# USB_Module_SchDoc.net
KiCad netlist of a schematic drawn in Altium Designer
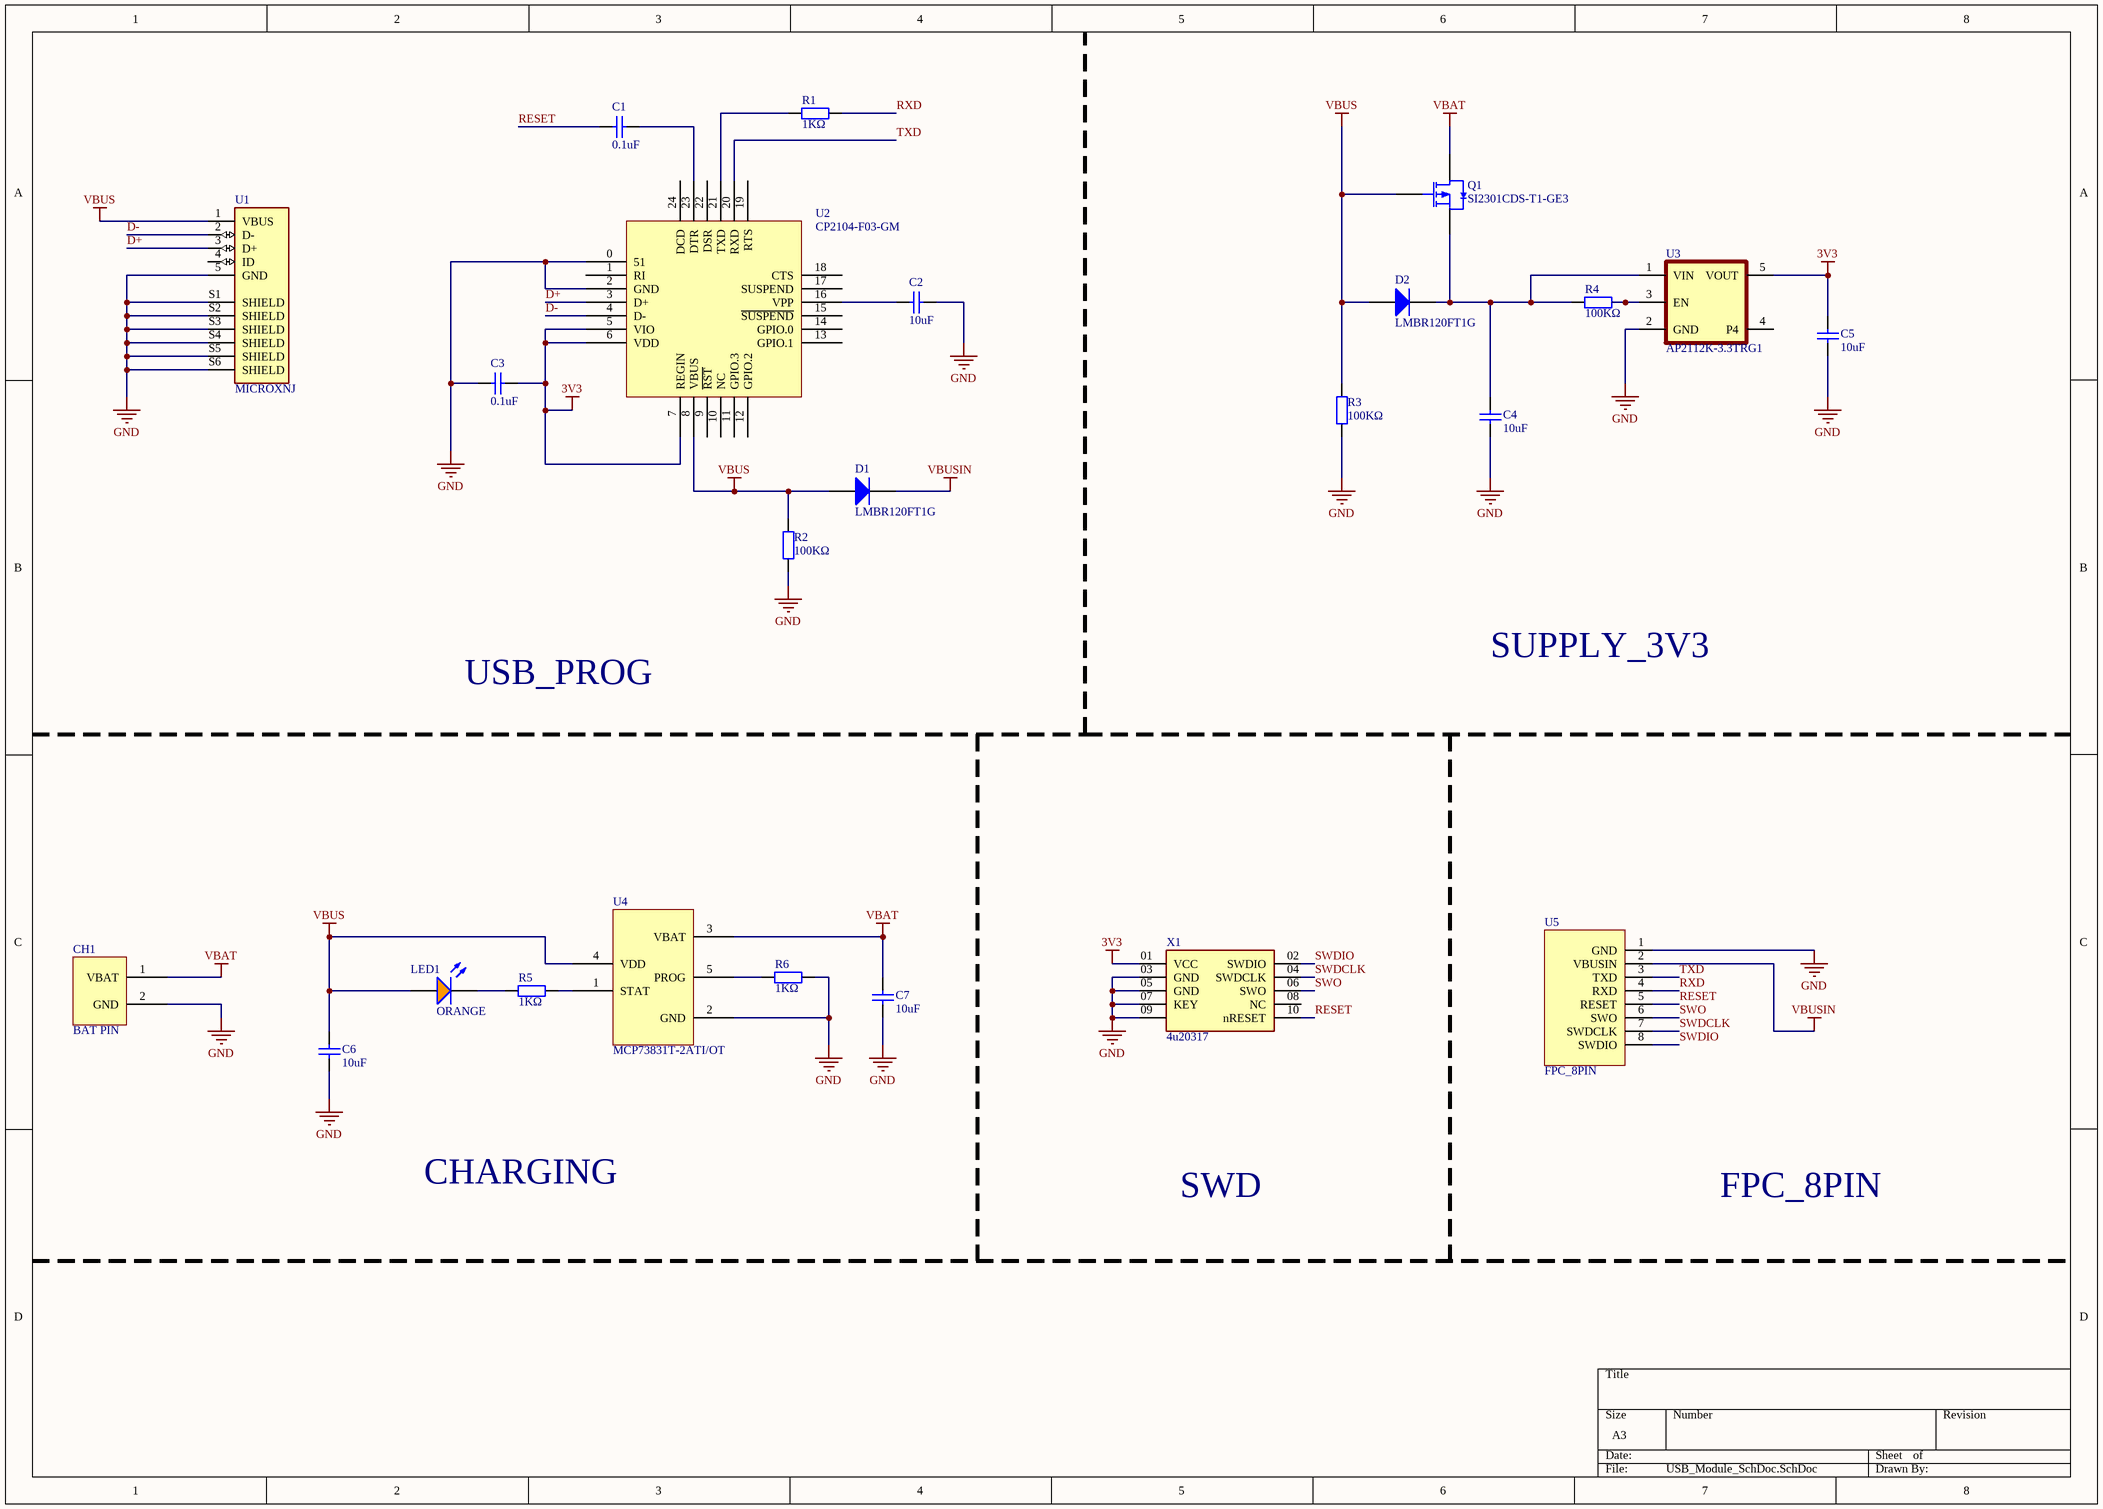
[diagram p0: USB_Module_SchDoc.SchDoc]

(export (version "E")
  (design (tool "Eeschema 10.0.6"))
  (components
    (comp (ref "C1")
      (value "0.1uF")
      (footprint "0603_C")
      (description "capacitance")
      (libsource (lib "magjoint_MCU") (part "CAP_0.1uF"))
    )
    (comp (ref "C2")
      (value "10uF")
      (footprint "0805_C")
      (description "capacitance")
      (libsource (lib "magjoint_MCU") (part "CAP_10uF"))
    )
    (comp (ref "C3")
      (value "0.1uF")
      (footprint "0603_C")
      (description "capacitance")
      (libsource (lib "magjoint_MCU") (part "CAP_0.1uF"))
    )
    (comp (ref "C4")
      (value "10uF")
      (footprint "0805_C")
      (description "capacitance")
      (libsource (lib "magjoint_MCU") (part "CAP_10uF"))
    )
    (comp (ref "C5")
      (value "10uF")
      (footprint "0805_C")
      (description "capacitance")
      (libsource (lib "magjoint_MCU") (part "CAP_10uF"))
    )
    (comp (ref "C6")
      (value "10uF")
      (footprint "0805_C")
      (description "capacitance")
      (libsource (lib "magjoint_MCU") (part "CAP_10uF"))
    )
    (comp (ref "C7")
      (value "10uF")
      (footprint "0805_C")
      (description "capacitance")
      (libsource (lib "magjoint_MCU") (part "CAP_10uF"))
    )
    (comp (ref "CH1")
      (value "BAT PIN")
      (footprint "BAT_MX 1.25-WI-2P")
      (description "button cell battary holder BS-08-B2AA025")
      (libsource (lib "magjoint_MCU") (part "BAT"))
    )
    (comp (ref "D1")
      (value "LMBR120FT1G")
      (footprint "SOD-123")
      (description "schottky diode")
      (libsource (lib "magjoint_MCU") (part "DIO_5"))
    )
    (comp (ref "D2")
      (value "LMBR120FT1G")
      (footprint "SOD-123")
      (description "schottky diode")
      (libsource (lib "magjoint_MCU") (part "DIO_5"))
    )
    (comp (ref "LED1")
      (value "ORANGE")
      (footprint "0603_LED_S1")
      (description "LED")
      (libsource (lib "MAGNETO") (part "LED_ORANGE"))
    )
    (comp (ref "Q1")
      (value "SI2301CDS-T1-GE3")
      (footprint "SOT-23(SOT-23-3)")
      (description "field effect tube")
      (libsource (lib "magjoint_MCU") (part "MOS"))
    )
    (comp (ref "R1")
      (value "1KΩ")
      (footprint "0603_R")
      (description "resistance")
      (libsource (lib "magjoint_MCU") (part "RES_1KΩ"))
    )
    (comp (ref "R2")
      (value "100KΩ")
      (footprint "0603_R")
      (description "resistance")
      (libsource (lib "magjoint_MCU") (part "RES_100KΩ"))
    )
    (comp (ref "R3")
      (value "100KΩ")
      (footprint "0603_R")
      (description "resistance")
      (libsource (lib "magjoint_MCU") (part "RES_100KΩ"))
    )
    (comp (ref "R4")
      (value "100KΩ")
      (footprint "0603_R")
      (description "resistance")
      (libsource (lib "") (part "RES_100KΩ_1"))
    )
    (comp (ref "R5")
      (value "1KΩ")
      (footprint "0603_R")
      (description "resistance")
      (libsource (lib "magjoint_MCU") (part "RES_1KΩ"))
    )
    (comp (ref "R6")
      (value "1KΩ")
      (footprint "0603_R")
      (description "resistance")
      (libsource (lib "magjoint_MCU") (part "RES_1KΩ"))
    )
    (comp (ref "U1")
      (value "MICROXNJ")
      (footprint "SHOUHAN_MICROXNJ")
      (description "Micro USB")
      (libsource (lib "magjoint_MCU") (part "MICROXNJ"))
    )
    (comp (ref "U2")
      (value "CP2104-F03-GM")
      (footprint "QFN-24_4x4x05P")
      (description "USB chip")
      (libsource (lib "magjoint_MCU") (part "CP2104"))
    )
    (comp (ref "U3")
      (value "AP2112K-3.3TRG1")
      (footprint "SOT95P285X140-5N")
      (description "LDO_ low dropout linear regulator")
      (libsource (lib "magjoint_MCU") (part "AP2112K"))
    )
    (comp (ref "U4")
      (value "MCP73831T-2ATI/OT")
      (footprint "SOT95P280X145-5N")
      (description "Battery power management chip")
      (libsource (lib "MAGNETO") (part "MCP73831T"))
    )
    (comp (ref "U5")
      (value "FPC_8PIN")
      (footprint "FPC0.5 2H-WS-8P")
      (libsource (lib "magjoint_MCU") (part "FPC_8PIN"))
    )
    (comp (ref "X1")
      (value "4u20317")
      (footprint "TFM-105-12-S-D-A")
      (description "Serial Wire (SW-DP) Connector")
      (libsource (lib "magjoint_MCU") (part "JTAG-CORTEXBOXPOSTS"))
    )
  )
  (nets
    (net (code "1") (name "/D+") (class "Default")
      (node (ref "U1") (pin "3") (pinfunction "D+_3") (pintype "bidirectional"))
      (node (ref "U2") (pin "3") (pinfunction "D+_3") (pintype "passive"))
    )
    (net (code "2") (name "/D-") (class "Default")
      (node (ref "U1") (pin "2") (pinfunction "D-_2") (pintype "bidirectional"))
      (node (ref "U2") (pin "4") (pinfunction "D-_4") (pintype "passive"))
    )
    (net (code "3") (name "/RESET") (class "Default")
      (node (ref "C1") (pin "1") (pinfunction "1_1") (pintype "passive"))
      (node (ref "U5") (pin "5") (pinfunction "RESET_5") (pintype "passive"))
      (node (ref "X1") (pin "10") (pinfunction "nRESET_10") (pintype "passive"))
    )
    (net (code "4") (name "/RXD") (class "Default")
      (node (ref "R1") (pin "2") (pinfunction "2_2") (pintype "passive"))
      (node (ref "U5") (pin "4") (pinfunction "RXD_4") (pintype "passive"))
    )
    (net (code "5") (name "/SWDCLK") (class "Default")
      (node (ref "U5") (pin "7") (pinfunction "SWDCLK_7") (pintype "passive"))
      (node (ref "X1") (pin "04") (pinfunction "SWDCLK_04") (pintype "passive"))
    )
    (net (code "6") (name "/SWDIO") (class "Default")
      (node (ref "U5") (pin "8") (pinfunction "SWDIO_8") (pintype "passive"))
      (node (ref "X1") (pin "02") (pinfunction "SWDIO_02") (pintype "passive"))
    )
    (net (code "7") (name "/SWO") (class "Default")
      (node (ref "U5") (pin "6") (pinfunction "SWO_6") (pintype "passive"))
      (node (ref "X1") (pin "06") (pinfunction "SWO_06") (pintype "passive"))
    )
    (net (code "8") (name "/TXD") (class "Default")
      (node (ref "U2") (pin "20") (pinfunction "RXD_20") (pintype "passive"))
      (node (ref "U5") (pin "3") (pinfunction "TXD_3") (pintype "passive"))
    )
    (net (code "9") (name "3V3") (class "Default")
      (node (ref "C3") (pin "2") (pinfunction "2_2") (pintype "passive"))
      (node (ref "C5") (pin "2") (pinfunction "2_2") (pintype "passive"))
      (node (ref "U2") (pin "5") (pinfunction "VIO_5") (pintype "passive"))
      (node (ref "U2") (pin "6") (pinfunction "VDD_6") (pintype "passive"))
      (node (ref "U2") (pin "7") (pinfunction "REGIN_7") (pintype "passive"))
      (node (ref "U3") (pin "5") (pinfunction "VOUT_5") (pintype "power_in"))
      (node (ref "X1") (pin "01") (pinfunction "VCC_01") (pintype "passive"))
    )
    (net (code "10") (name "GND") (class "Default")
      (node (ref "C2") (pin "2") (pinfunction "2_2") (pintype "passive"))
      (node (ref "C3") (pin "1") (pinfunction "1_1") (pintype "passive"))
      (node (ref "C4") (pin "1") (pinfunction "1_1") (pintype "passive"))
      (node (ref "C5") (pin "1") (pinfunction "1_1") (pintype "passive"))
      (node (ref "C6") (pin "1") (pinfunction "1_1") (pintype "passive"))
      (node (ref "C7") (pin "1") (pinfunction "1_1") (pintype "passive"))
      (node (ref "CH1") (pin "2") (pinfunction "GND_2") (pintype "passive"))
      (node (ref "R2") (pin "1") (pinfunction "1_1") (pintype "passive"))
      (node (ref "R3") (pin "1") (pinfunction "1_1") (pintype "passive"))
      (node (ref "R6") (pin "2") (pinfunction "2_2") (pintype "passive"))
      (node (ref "U1") (pin "5") (pinfunction "GND_5") (pintype "power_in"))
      (node (ref "U1") (pin "S1") (pinfunction "SHIELD_S1") (pintype "passive"))
      (node (ref "U1") (pin "S2") (pinfunction "SHIELD_S2") (pintype "passive"))
      (node (ref "U1") (pin "S3") (pinfunction "SHIELD_S3") (pintype "passive"))
      (node (ref "U1") (pin "S4") (pinfunction "SHIELD_S4") (pintype "passive"))
      (node (ref "U1") (pin "S5") (pinfunction "SHIELD_S5") (pintype "passive"))
      (node (ref "U1") (pin "S6") (pinfunction "SHIELD_S6") (pintype "passive"))
      (node (ref "U2") (pin "0") (pinfunction "51_0") (pintype "passive"))
      (node (ref "U2") (pin "2") (pinfunction "GND_2") (pintype "passive"))
      (node (ref "U3") (pin "2") (pinfunction "GND_2") (pintype "power_in"))
      (node (ref "U4") (pin "2") (pinfunction "GND_2") (pintype "passive"))
      (node (ref "U5") (pin "1") (pinfunction "GND_1") (pintype "passive"))
      (node (ref "X1") (pin "03") (pinfunction "GND_03") (pintype "passive"))
      (node (ref "X1") (pin "05") (pinfunction "GND_05") (pintype "passive"))
      (node (ref "X1") (pin "07") (pinfunction "KEY_07") (pintype "passive"))
      (node (ref "X1") (pin "09") (pinfunction "GNDDetect_09") (pintype "passive"))
    )
    (net (code "11") (name "Net-(D2-K)") (class "Default")
      (node (ref "C4") (pin "2") (pinfunction "2_2") (pintype "passive"))
      (node (ref "D2") (pin "2") (pinfunction "K_2") (pintype "passive"))
      (node (ref "Q1") (pin "2") (pinfunction "S_2") (pintype "passive"))
      (node (ref "R4") (pin "1") (pinfunction "1_1") (pintype "passive"))
      (node (ref "U3") (pin "1") (pinfunction "VIN_1") (pintype "power_in"))
    )
    (net (code "12") (name "Net-(LED1-PadK)") (class "Default")
      (node (ref "LED1") (pin "K") (pinfunction "K_K") (pintype "passive"))
      (node (ref "R5") (pin "1") (pinfunction "1_1") (pintype "passive"))
    )
    (net (code "13") (name "Net-(U2-DTR)") (class "Default")
      (node (ref "C1") (pin "2") (pinfunction "2_2") (pintype "passive"))
      (node (ref "U2") (pin "23") (pinfunction "DTR_23") (pintype "passive"))
    )
    (net (code "14") (name "Net-(U2-TXD)") (class "Default")
      (node (ref "R1") (pin "1") (pinfunction "1_1") (pintype "passive"))
      (node (ref "U2") (pin "21") (pinfunction "TXD_21") (pintype "passive"))
    )
    (net (code "15") (name "Net-(U2-VPP)") (class "Default")
      (node (ref "C2") (pin "1") (pinfunction "1_1") (pintype "passive"))
      (node (ref "U2") (pin "16") (pinfunction "VPP_16") (pintype "passive"))
    )
    (net (code "16") (name "Net-(U3-EN)") (class "Default")
      (node (ref "R4") (pin "2") (pinfunction "2_2") (pintype "passive"))
      (node (ref "U3") (pin "3") (pinfunction "EN_3") (pintype "power_in"))
    )
    (net (code "17") (name "Net-(U4-PROG)") (class "Default")
      (node (ref "R6") (pin "1") (pinfunction "1_1") (pintype "passive"))
      (node (ref "U4") (pin "5") (pinfunction "PROG_5") (pintype "passive"))
    )
    (net (code "18") (name "Net-(U4-STAT)") (class "Default")
      (node (ref "R5") (pin "2") (pinfunction "2_2") (pintype "passive"))
      (node (ref "U4") (pin "1") (pinfunction "STAT_1") (pintype "passive"))
    )
    (net (code "19") (name "VBAT") (class "Default")
      (node (ref "C7") (pin "2") (pinfunction "2_2") (pintype "passive"))
      (node (ref "CH1") (pin "1") (pinfunction "VBAT_1") (pintype "passive"))
      (node (ref "Q1") (pin "3") (pinfunction "D_3") (pintype "passive"))
      (node (ref "U4") (pin "3") (pinfunction "VBAT_3") (pintype "passive"))
    )
    (net (code "20") (name "VBUS") (class "Default")
      (node (ref "C6") (pin "2") (pinfunction "2_2") (pintype "passive"))
      (node (ref "D1") (pin "1") (pinfunction "A_1") (pintype "passive"))
      (node (ref "D2") (pin "1") (pinfunction "A_1") (pintype "passive"))
      (node (ref "LED1") (pin "A") (pinfunction "A_A") (pintype "passive"))
      (node (ref "Q1") (pin "1") (pinfunction "G_1") (pintype "passive"))
      (node (ref "R2") (pin "2") (pinfunction "2_2") (pintype "passive"))
      (node (ref "R3") (pin "2") (pinfunction "2_2") (pintype "passive"))
      (node (ref "U1") (pin "1") (pinfunction "VBUS_1") (pintype "power_in"))
      (node (ref "U2") (pin "8") (pinfunction "VBUS_8") (pintype "passive"))
      (node (ref "U4") (pin "4") (pinfunction "VDD_4") (pintype "passive"))
    )
    (net (code "21") (name "VBUSIN") (class "Default")
      (node (ref "D1") (pin "2") (pinfunction "K_2") (pintype "passive"))
      (node (ref "U5") (pin "2") (pinfunction "VBUSIN_2") (pintype "passive"))
    )
    (net (code "22") (name "unconnected-(U1-ID-Pad4)") (class "Default")
      (node (ref "U1") (pin "4") (pinfunction "ID_4") (pintype "bidirectional"))
    )
    (net (code "23") (name "unconnected-(U2-CTS-Pad18)") (class "Default")
      (node (ref "U2") (pin "18") (pinfunction "CTS_18") (pintype "passive"))
    )
    (net (code "24") (name "unconnected-(U2-DCD-Pad24)") (class "Default")
      (node (ref "U2") (pin "24") (pinfunction "DCD_24") (pintype "passive"))
    )
    (net (code "25") (name "unconnected-(U2-DSR-Pad22)") (class "Default")
      (node (ref "U2") (pin "22") (pinfunction "DSR_22") (pintype "passive"))
    )
    (net (code "26") (name "unconnected-(U2-GPIO.0-Pad14)") (class "Default")
      (node (ref "U2") (pin "14") (pinfunction "GPIO.0_14") (pintype "passive"))
    )
    (net (code "27") (name "unconnected-(U2-GPIO.1-Pad13)") (class "Default")
      (node (ref "U2") (pin "13") (pinfunction "GPIO.1_13") (pintype "passive"))
    )
    (net (code "28") (name "unconnected-(U2-GPIO.2-Pad12)") (class "Default")
      (node (ref "U2") (pin "12") (pinfunction "GPIO.2_12") (pintype "passive"))
    )
    (net (code "29") (name "unconnected-(U2-GPIO.3-Pad11)") (class "Default")
      (node (ref "U2") (pin "11") (pinfunction "GPIO.3_11") (pintype "passive"))
    )
    (net (code "30") (name "unconnected-(U2-NC-Pad10)") (class "Default")
      (node (ref "U2") (pin "10") (pinfunction "NC_10") (pintype "passive"))
    )
    (net (code "31") (name "unconnected-(U2-RI-Pad1)") (class "Default")
      (node (ref "U2") (pin "1") (pinfunction "RI_1") (pintype "passive"))
    )
    (net (code "32") (name "unconnected-(U2-RTS-Pad19)") (class "Default")
      (node (ref "U2") (pin "19") (pinfunction "RTS_19") (pintype "passive"))
    )
    (net (code "33") (name "unconnected-(U2-SUSPEND-Pad17)") (class "Default")
      (node (ref "U2") (pin "17") (pinfunction "SUSPEND_17") (pintype "passive"))
    )
    (net (code "34") (name "unconnected-(U2-~{RST}-Pad9)") (class "Default")
      (node (ref "U2") (pin "9") (pinfunction "~{RST}_9") (pintype "passive"))
    )
    (net (code "35") (name "unconnected-(U2-~{SUSPEND}-Pad15)") (class "Default")
      (node (ref "U2") (pin "15") (pinfunction "~{SUSPEND}_15") (pintype "passive"))
    )
    (net (code "36") (name "unconnected-(U3-P4-Pad4)") (class "Default")
      (node (ref "U3") (pin "4") (pinfunction "P4_4") (pintype "power_in"))
    )
    (net (code "37") (name "unconnected-(X1-NC-Pad08)") (class "Default")
      (node (ref "X1") (pin "08") (pinfunction "NC_08") (pintype "passive"))
    )
  )
)
